# remoteFK01.net
KiCad netlist of a schematic drawn in Altium Designer
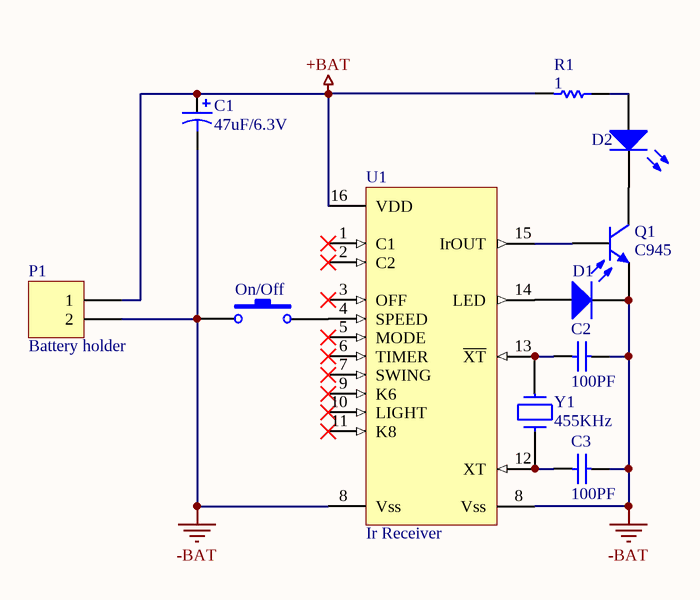
[diagram p0: remoteFK01.SchDoc]

(export (version "E")
  (design (tool "Eeschema 10.0.6"))
  (components
    (comp (ref "C1")
      (value "47uF/6.3V")
      (footprint "RB.1/.2")
      (description "Polarized Capacitor (SMD)")
      (fields (field (name "PUBLISHER") "Altium Limited"))
      (libsource (lib "Miscellaneous Devices") (part "Cap Pol1"))
    )
    (comp (ref "C2")
      (value "100PF")
      (footprint "RAD0.1")
      (description "Capacitor np")
      (fields (field (name "PUBLISHER") "Altium Limited"))
      (libsource (lib "MySchLib") (part "Cap"))
    )
    (comp (ref "C3")
      (value "100PF")
      (footprint "RAD0.1")
      (description "Capacitor np")
      (fields (field (name "PUBLISHER") "Altium Limited"))
      (libsource (lib "MySchLib") (part "Cap"))
    )
    (comp (ref "D1")
      (value "Red")
      (footprint "LED0.3")
      (description "LED Radial 0.3")
      (fields (field (name "PUBLISHER") "Altium Limited"))
      (libsource (lib "MySchLib") (part "LED0.5"))
    )
    (comp (ref "D2")
      (value "Ir Transmitter")
      (footprint "LED0.5-L")
      (description "LED Radial 0.5")
      (fields (field (name "PUBLISHER") "Altium Limited"))
      (libsource (lib "") (part "LED0.5_1"))
    )
    (comp (ref "P1")
      (value "Battery holder")
      (footprint "BatHol22")
      (description "Header, 2-Pin")
      (fields (field (name "PUBLISHER") "Altium Limited"))
      (libsource (lib "Miscellaneous Connectors") (part "Header 2"))
    )
    (comp (ref "Q1")
      (value "C945")
      (footprint "TO92BS2")
      (description "NPN General Purpose Amplifier")
      (fields (field (name "PUBLISHER") "Altium Limited"))
      (libsource (lib "MySchLib") (part "BC337"))
    )
    (comp (ref "R1")
      (value "1")
      (footprint "RES0.35")
      (description "Resistor")
      (fields (field (name "PUBLISHER") "Altium Limited"))
      (libsource (lib "MySchLib") (part "Resistor"))
    )
    (comp (ref "S1")
      (value "On/Off")
      (footprint "PUSHBOT2")
      (description "6x6x5")
      (fields (field (name "PUBLISHER") "Altium Limited"))
      (libsource (lib "MySchLib") (part "SW-PB"))
    )
    (comp (ref "U1")
      (value "Ir Receiver")
      (footprint "SOIC16")
      (description "Fan Ir. Receiver")
      (libsource (lib "MySchLib") (part "SC5104"))
    )
    (comp (ref "Y1")
      (value "455KHz")
      (footprint "XTALRLOB")
      (description "Crystal")
      (libsource (lib "MySchLib") (part "CRYSTAL"))
    )
  )
  (nets
    (net (code "1") (name "+BAT") (class "Default")
      (node (ref "C1") (pin "1") (pinfunction "1_1") (pintype "passive"))
      (node (ref "P1") (pin "1") (pinfunction "1_1") (pintype "passive"))
      (node (ref "R1") (pin "2") (pinfunction "2_2") (pintype "passive"))
      (node (ref "U1") (pin "16") (pinfunction "VDD_16") (pintype "power_in"))
    )
    (net (code "2") (name "-BAT") (class "Default")
      (node (ref "C1") (pin "2") (pinfunction "2_2") (pintype "passive"))
      (node (ref "C2") (pin "1") (pinfunction "1_1") (pintype "passive"))
      (node (ref "C3") (pin "1") (pinfunction "1_1") (pintype "passive"))
      (node (ref "D1") (pin "2") (pinfunction "K_2") (pintype "passive"))
      (node (ref "P1") (pin "2") (pinfunction "2_2") (pintype "passive"))
      (node (ref "Q1") (pin "3") (pinfunction "E_3") (pintype "passive"))
      (node (ref "S1") (pin "1") (pinfunction "1_1") (pintype "passive"))
      (node (ref "U1") (pin "8") (pinfunction "Vss_8") (pintype "power_in"))
    )
    (net (code "3") (name "Net-(D1-A)") (class "Default")
      (node (ref "D1") (pin "1") (pinfunction "A_1") (pintype "passive"))
      (node (ref "U1") (pin "14") (pinfunction "LED_14") (pintype "output"))
    )
    (net (code "4") (name "Net-(D2-A)") (class "Default")
      (node (ref "D2") (pin "1") (pinfunction "A_1") (pintype "passive"))
      (node (ref "R1") (pin "1") (pinfunction "1_1") (pintype "passive"))
    )
    (net (code "5") (name "Net-(D2-K)") (class "Default")
      (node (ref "D2") (pin "2") (pinfunction "K_2") (pintype "passive"))
      (node (ref "Q1") (pin "2") (pinfunction "C_2") (pintype "passive"))
    )
    (net (code "6") (name "Net-(Q1-B)") (class "Default")
      (node (ref "Q1") (pin "1") (pinfunction "B_1") (pintype "passive"))
      (node (ref "U1") (pin "15") (pinfunction "IrOUT_15") (pintype "output"))
    )
    (net (code "7") (name "Net-(U1-SPEED)") (class "Default")
      (node (ref "S1") (pin "2") (pinfunction "2_2") (pintype "passive"))
      (node (ref "U1") (pin "4") (pinfunction "SPEED_4") (pintype "input"))
    )
    (net (code "8") (name "Net-(U1-XT)") (class "Default")
      (node (ref "C3") (pin "2") (pinfunction "2_2") (pintype "passive"))
      (node (ref "U1") (pin "12") (pinfunction "XT_12") (pintype "input"))
      (node (ref "Y1") (pin "2") (pinfunction "2_2") (pintype "passive"))
    )
    (net (code "9") (name "Net-(U1-~{XT})") (class "Default")
      (node (ref "C2") (pin "2") (pinfunction "2_2") (pintype "passive"))
      (node (ref "U1") (pin "13") (pinfunction "~{XT}_13") (pintype "input"))
      (node (ref "Y1") (pin "1") (pinfunction "1_1") (pintype "passive"))
    )
    (net (code "10") (name "unconnected-(U1-C1-Pad1)") (class "Default")
      (node (ref "U1") (pin "1") (pinfunction "C1_1") (pintype "input+no_connect"))
    )
    (net (code "11") (name "unconnected-(U1-C2-Pad2)") (class "Default")
      (node (ref "U1") (pin "2") (pinfunction "C2_2") (pintype "input+no_connect"))
    )
    (net (code "12") (name "unconnected-(U1-K6-Pad9)") (class "Default")
      (node (ref "U1") (pin "9") (pinfunction "K6_9") (pintype "input+no_connect"))
    )
    (net (code "13") (name "unconnected-(U1-K8-Pad11)") (class "Default")
      (node (ref "U1") (pin "11") (pinfunction "K8_11") (pintype "input+no_connect"))
    )
    (net (code "14") (name "unconnected-(U1-LIGHT-Pad10)") (class "Default")
      (node (ref "U1") (pin "10") (pinfunction "LIGHT_10") (pintype "input+no_connect"))
    )
    (net (code "15") (name "unconnected-(U1-MODE-Pad5)") (class "Default")
      (node (ref "U1") (pin "5") (pinfunction "MODE_5") (pintype "input+no_connect"))
    )
    (net (code "16") (name "unconnected-(U1-OFF-Pad3)") (class "Default")
      (node (ref "U1") (pin "3") (pinfunction "OFF_3") (pintype "input+no_connect"))
    )
    (net (code "17") (name "unconnected-(U1-SWING-Pad7)") (class "Default")
      (node (ref "U1") (pin "7") (pinfunction "SWING_7") (pintype "input+no_connect"))
    )
    (net (code "18") (name "unconnected-(U1-TIMER-Pad6)") (class "Default")
      (node (ref "U1") (pin "6") (pinfunction "TIMER_6") (pintype "input+no_connect"))
    )
  )
)
